# BMS.net
KiCad netlist of a schematic drawn in Altium Designer
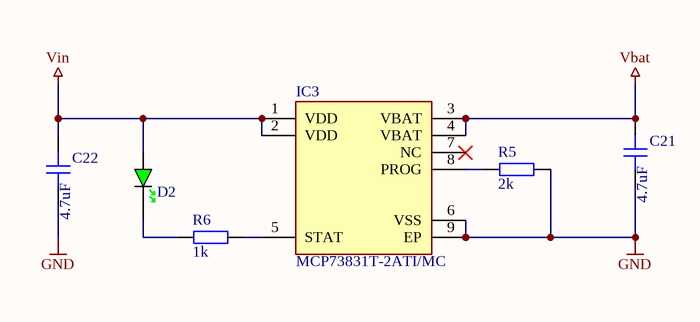
[diagram p0: BMS.SchDoc]

(export (version "E")
  (design (tool "Eeschema 10.0.6"))
  (components
    (comp (ref "C21")
      (value "4.7uF")
      (footprint "CAP_0402")
      (description "Capacitor SMD 0402 10V")
      (fields (field (name "Comment") "C0402_10V"))
      (libsource (lib "Schematic-Lib-PhilsLab") (part "CAP_0402_10V"))
    )
    (comp (ref "C22")
      (value "4.7uF")
      (footprint "CAP_0402")
      (description "Capacitor SMD 0402 10V")
      (fields (field (name "Comment") "C0402_10V"))
      (libsource (lib "Schematic-Lib-PhilsLab") (part "CAP_0402_10V"))
    )
    (comp (ref "D2")
      (value "GREEN")
      (footprint "LED_0402_GREEN")
      (description "LED 0402 GREEN SMD")
      (libsource (lib "Schematic-Lib-PhilsLab") (part "LED_0402_GREEN"))
    )
    (comp (ref "IC3")
      (value "MCP73831T-2ATI/MC")
      (footprint "Footprint-Lib-PhilsLab:SON65P300X300X80-9N-D")
      (description "Battery Management Charge mgnt contr")
      (fields (field (name "MOUSER PART NUMBER") "579-MCP73831T-2ATIMC"))
      (libsource (lib "Schematic-Lib-PhilsLab") (part "MCP73831T-2ATI/MC"))
    )
    (comp (ref "R5")
      (value "2k")
      (footprint "RES_0402")
      (description "Resistor SMD 0402")
      (fields (field (name "Comment") "R0402"))
      (libsource (lib "Schematic-Lib-PhilsLab") (part "RES_0402"))
    )
    (comp (ref "R6")
      (value "1k")
      (footprint "RES_0402")
      (description "Resistor SMD 0402")
      (fields (field (name "Comment") "R0402"))
      (libsource (lib "Schematic-Lib-PhilsLab") (part "RES_0402"))
    )
  )
  (nets
    (net (code "1") (name "GND") (class "Default")
      (node (ref "C21") (pin "1") (pinfunction "1_1") (pintype "passive"))
      (node (ref "C22") (pin "1") (pinfunction "1_1") (pintype "passive"))
      (node (ref "IC3") (pin "6") (pinfunction "VSS_6") (pintype "passive"))
      (node (ref "IC3") (pin "9") (pinfunction "EP_9") (pintype "passive"))
      (node (ref "R5") (pin "2") (pinfunction "2_2") (pintype "passive"))
    )
    (net (code "2") (name "Net-(D2-PadK)") (class "Default")
      (node (ref "D2") (pin "K") (pinfunction "K_K") (pintype "passive"))
      (node (ref "R6") (pin "1") (pinfunction "1_1") (pintype "passive"))
    )
    (net (code "3") (name "Net-(IC3-PROG)") (class "Default")
      (node (ref "IC3") (pin "8") (pinfunction "PROG_8") (pintype "passive"))
      (node (ref "R5") (pin "1") (pinfunction "1_1") (pintype "passive"))
    )
    (net (code "4") (name "Net-(IC3-STAT)") (class "Default")
      (node (ref "IC3") (pin "5") (pinfunction "STAT_5") (pintype "passive"))
      (node (ref "R6") (pin "2") (pinfunction "2_2") (pintype "passive"))
    )
    (net (code "5") (name "Vbat") (class "Default")
      (node (ref "C21") (pin "2") (pinfunction "2_2") (pintype "passive"))
      (node (ref "IC3") (pin "3") (pinfunction "VBAT_3") (pintype "passive"))
      (node (ref "IC3") (pin "4") (pinfunction "VBAT_4") (pintype "passive"))
    )
    (net (code "6") (name "Vin") (class "Default")
      (node (ref "C22") (pin "2") (pinfunction "2_2") (pintype "passive"))
      (node (ref "D2") (pin "A") (pinfunction "A_A") (pintype "passive"))
      (node (ref "IC3") (pin "1") (pinfunction "VDD_1") (pintype "passive"))
      (node (ref "IC3") (pin "2") (pinfunction "VDD_2") (pintype "passive"))
    )
    (net (code "7") (name "unconnected-(IC3-NC-Pad7)") (class "Default")
      (node (ref "IC3") (pin "7") (pinfunction "NC_7") (pintype "passive+no_connect"))
    )
  )
)
